# CPLD.net
KiCad netlist of a schematic drawn in Altium Designer
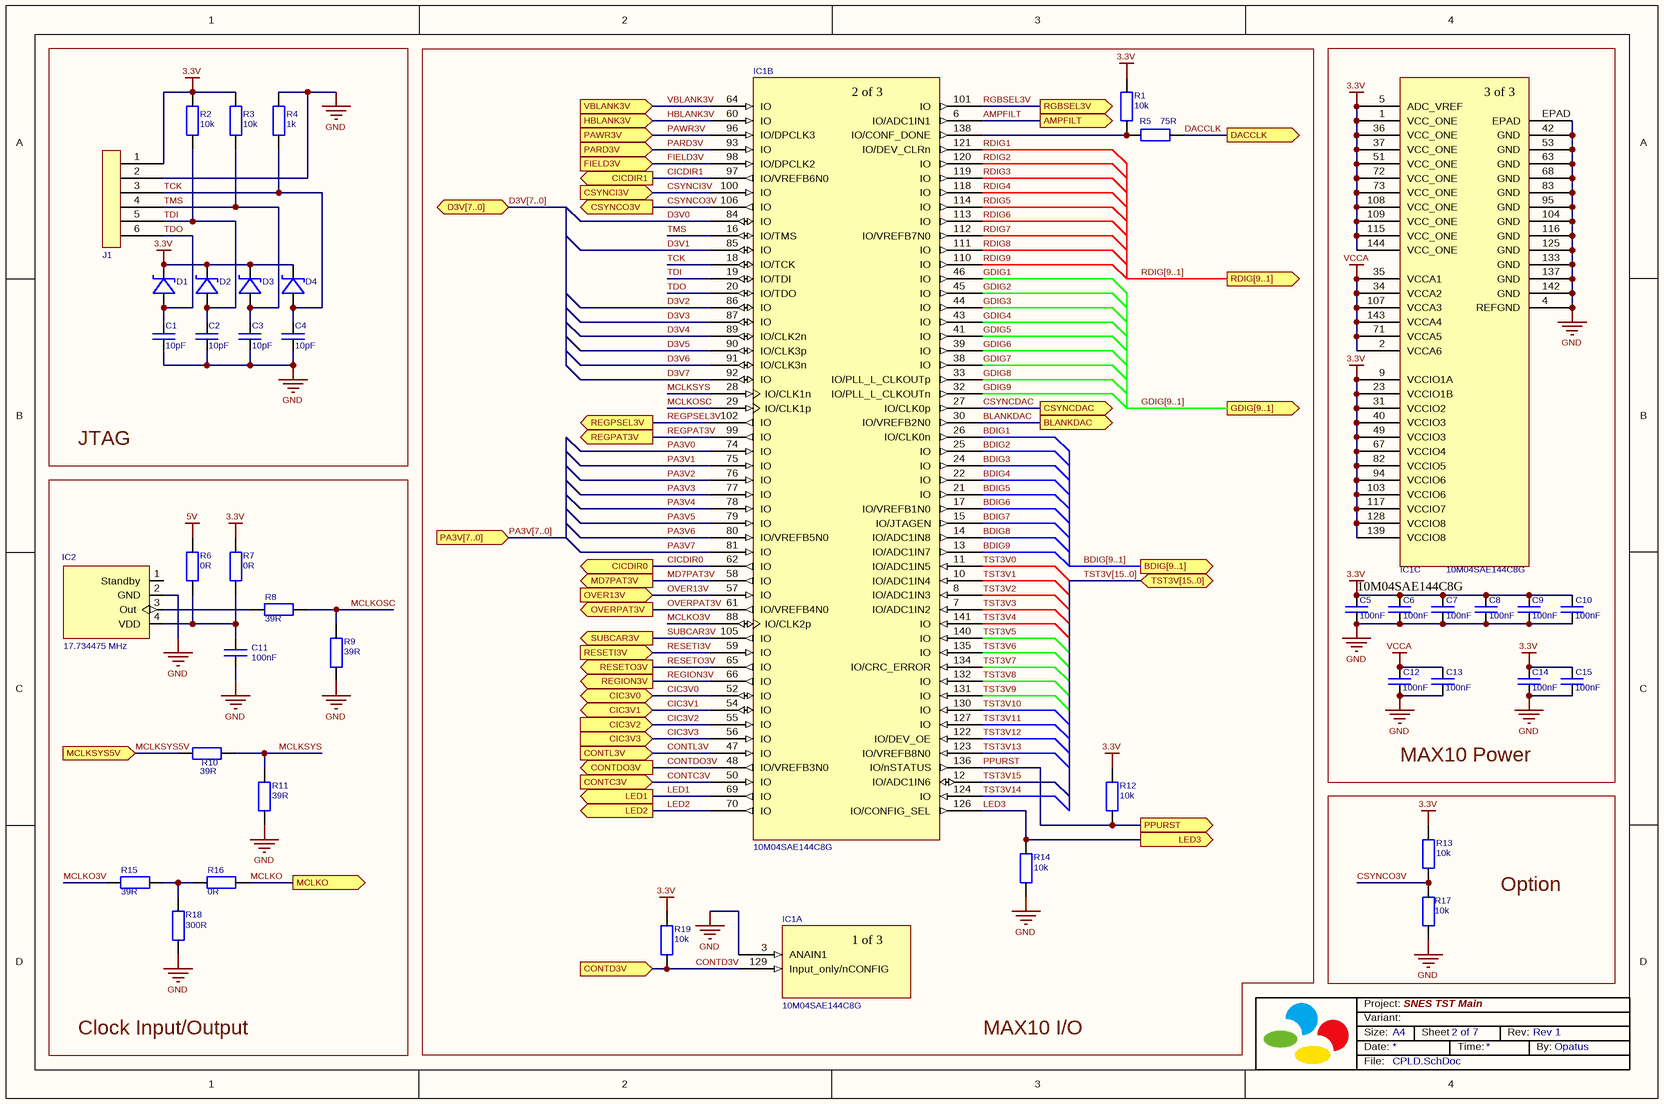
[diagram p0: CPLD.SchDoc]

(export (version "E")
  (design (tool "Eeschema 10.0.6"))
  (components
    (comp (ref "C1")
      (value "10pF")
      (footprint "Cap_0402_Chip")
      (fields
        (field (name "TOLERANCE") "±20%")
        (field (name "Comment") "Ceramic Capacitor 10pF 10V ±20% X7R 0402")
      )
      (libsource (lib "PCB") (part "Capacitor"))
    )
    (comp (ref "C2")
      (value "10pF")
      (footprint "Cap_0402_Chip")
      (fields
        (field (name "TOLERANCE") "±20%")
        (field (name "Comment") "Ceramic Capacitor 10pF 10V ±20% X7R 0402")
      )
      (libsource (lib "PCB") (part "Capacitor"))
    )
    (comp (ref "C3")
      (value "10pF")
      (footprint "Cap_0402_Chip")
      (fields
        (field (name "TOLERANCE") "±20%")
        (field (name "Comment") "Ceramic Capacitor 10pF 10V ±20% X7R 0402")
      )
      (libsource (lib "PCB") (part "Capacitor"))
    )
    (comp (ref "C4")
      (value "10pF")
      (footprint "Cap_0402_Chip")
      (fields
        (field (name "TOLERANCE") "±20%")
        (field (name "Comment") "Ceramic Capacitor 10pF 10V ±20% X7R 0402")
      )
      (libsource (lib "PCB") (part "Capacitor"))
    )
    (comp (ref "C5")
      (value "100nF")
      (footprint "Cap_0402_Chip")
      (fields
        (field (name "TOLERANCE") "±20%")
        (field (name "Comment") "Ceramic Capacitor 100nF 10V ±20% X7R 0402")
      )
      (libsource (lib "PCB") (part "Capacitor"))
    )
    (comp (ref "C6")
      (value "100nF")
      (footprint "Cap_0402_Chip")
      (fields
        (field (name "TOLERANCE") "±20%")
        (field (name "Comment") "Ceramic Capacitor 100nF 10V ±20% X7R 0402")
      )
      (libsource (lib "PCB") (part "Capacitor"))
    )
    (comp (ref "C7")
      (value "100nF")
      (footprint "Cap_0402_Chip")
      (fields
        (field (name "TOLERANCE") "±20%")
        (field (name "Comment") "Ceramic Capacitor 100nF 10V ±20% X7R 0402")
      )
      (libsource (lib "PCB") (part "Capacitor"))
    )
    (comp (ref "C8")
      (value "100nF")
      (footprint "Cap_0402_Chip")
      (fields
        (field (name "TOLERANCE") "±20%")
        (field (name "Comment") "Ceramic Capacitor 100nF 10V ±20% X7R 0402")
      )
      (libsource (lib "PCB") (part "Capacitor"))
    )
    (comp (ref "C9")
      (value "100nF")
      (footprint "Cap_0402_Chip")
      (fields
        (field (name "TOLERANCE") "±20%")
        (field (name "Comment") "Ceramic Capacitor 100nF 10V ±20% X7R 0402")
      )
      (libsource (lib "PCB") (part "Capacitor"))
    )
    (comp (ref "C10")
      (value "100nF")
      (footprint "Cap_0402_Chip")
      (fields
        (field (name "TOLERANCE") "±20%")
        (field (name "Comment") "Ceramic Capacitor 100nF 10V ±20% X7R 0402")
      )
      (libsource (lib "PCB") (part "Capacitor"))
    )
    (comp (ref "C11")
      (value "100nF")
      (footprint "Cap_0402_Chip")
      (fields
        (field (name "TOLERANCE") "±20%")
        (field (name "Comment") "Ceramic Capacitor 100nF 10V ±20% X7R 0402")
      )
      (libsource (lib "PCB") (part "Capacitor"))
    )
    (comp (ref "C12")
      (value "100nF")
      (footprint "Cap_0402_Chip")
      (fields
        (field (name "TOLERANCE") "±20%")
        (field (name "Comment") "Ceramic Capacitor 100nF 10V ±20% X7R 0402")
      )
      (libsource (lib "PCB") (part "Capacitor"))
    )
    (comp (ref "C13")
      (value "100nF")
      (footprint "Cap_0402_Chip")
      (fields
        (field (name "TOLERANCE") "±20%")
        (field (name "Comment") "Ceramic Capacitor 100nF 10V ±20% X7R 0402")
      )
      (libsource (lib "PCB") (part "Capacitor"))
    )
    (comp (ref "C14")
      (value "100nF")
      (footprint "Cap_0402_Chip")
      (fields
        (field (name "TOLERANCE") "±20%")
        (field (name "Comment") "Ceramic Capacitor 100nF 10V ±20% X7R 0402")
      )
      (libsource (lib "PCB") (part "Capacitor"))
    )
    (comp (ref "C15")
      (value "100nF")
      (footprint "Cap_0402_Chip")
      (fields
        (field (name "TOLERANCE") "±20%")
        (field (name "Comment") "Ceramic Capacitor 100nF 10V ±20% X7R 0402")
      )
      (libsource (lib "PCB") (part "Capacitor"))
    )
    (comp (ref "D1")
      (value "BAT54WS")
      (footprint "SOD323")
      (description "Schottky Diode")
      (fields (field (name "MANUFACTURER_PART_NUMBER") "BAT54WS-7-F") (field (name "MANUFACTURER") "Diodes"))
      (libsource (lib "PCB") (part "Schottky Diode"))
    )
    (comp (ref "D2")
      (value "BAT54WS")
      (footprint "SOD323")
      (description "Schottky Diode")
      (fields (field (name "MANUFACTURER_PART_NUMBER") "BAT54WS-7-F") (field (name "MANUFACTURER") "Diodes"))
      (libsource (lib "PCB") (part "Schottky Diode"))
    )
    (comp (ref "D3")
      (value "BAT54WS")
      (footprint "SOD323")
      (description "Schottky Diode")
      (fields (field (name "MANUFACTURER_PART_NUMBER") "BAT54WS-7-F") (field (name "MANUFACTURER") "Diodes"))
      (libsource (lib "PCB") (part "Schottky Diode"))
    )
    (comp (ref "D4")
      (value "BAT54WS")
      (footprint "SOD323")
      (description "Schottky Diode")
      (fields (field (name "MANUFACTURER_PART_NUMBER") "BAT54WS-7-F") (field (name "MANUFACTURER") "Diodes"))
      (libsource (lib "PCB") (part "Schottky Diode"))
    )
    (comp (ref "IC1")
      (value "10M04SAE144C8G")
      (footprint "EQFP-144_A:1P65_")
      (description "No Description Available")
      (fields
        (field (name "MANUFACTURER") "Intel")
        (field (name "MANUFACTURER_PART_NUMBER") "10M04SAE144C8G")
        (field (name "COPYRIGHT") "Copyright (C) 2018 Accelerated Designs. All rights reserved")
      )
      (libsource (lib "PCB") (part "10M08SAE144C8G"))
    )
    (comp (ref "IC2")
      (value "17.734475 MHz")
      (footprint "Quarz 7.5mm")
      (description "Oscillator")
      (fields
        (field (name "FREQUENCY") "17.734475 MHz")
        (field (name "MANUFACTURER") "IQD Frequency")
        (field (name "MANUFACTURER_PART_NUMBER") "LFSPXO020648Bulk")
      )
      (libsource (lib "PCB") (part "Oscillator"))
    )
    (comp (ref "J1")
      (value "Conn 6P")
      (footprint "Con6P")
      (description "6 Pole Connector")
      (libsource (lib "PCB") (part "Conn 6P"))
    )
    (comp (ref "R1")
      (value "10k")
      (footprint "Res_0402_Chip")
      (fields (field (name "TOLERANCE") "±1%") (field (name "Comment") "Resistor 10k 0402 ±1%"))
      (libsource (lib "PCB") (part "R"))
    )
    (comp (ref "R2")
      (value "10k")
      (footprint "Res_0402_Chip")
      (fields (field (name "TOLERANCE") "±1%") (field (name "Comment") "Resistor 10k 0402 ±1%"))
      (libsource (lib "PCB") (part "R"))
    )
    (comp (ref "R3")
      (value "10k")
      (footprint "Res_0402_Chip")
      (fields (field (name "TOLERANCE") "±1%") (field (name "Comment") "Resistor 10k 0402 ±1%"))
      (libsource (lib "PCB") (part "R"))
    )
    (comp (ref "R4")
      (value "1k")
      (footprint "Res_0402_Chip")
      (fields (field (name "TOLERANCE") "±1%") (field (name "Comment") "Resistor 1k 0402 ±1%"))
      (libsource (lib "") (part "R_3"))
    )
    (comp (ref "R5")
      (value "75R")
      (footprint "Res_0402_Chip")
      (fields (field (name "TOLERANCE") "±1%") (field (name "Comment") "Resistor 75R 0402 ±1%"))
      (libsource (lib "") (part "R_1"))
    )
    (comp (ref "R6")
      (value "0R")
      (footprint "Res_0402_Chip")
      (fields (field (name "Comment") "Resistor 0R 0402 "))
      (libsource (lib "PCB") (part "R"))
    )
    (comp (ref "R7")
      (value "0R")
      (footprint "Res_0402_Chip")
      (fields (field (name "Comment") "Resistor 0R 0402 "))
      (libsource (lib "PCB") (part "R"))
    )
    (comp (ref "R8")
      (value "39R")
      (footprint "Res_0603_Chip")
      (fields (field (name "TOLERANCE") "±1%") (field (name "Comment") "Resistor 39R 0603 ±1%"))
      (libsource (lib "") (part "R_2"))
    )
    (comp (ref "R9")
      (value "39R")
      (footprint "Res_0603_Chip")
      (fields (field (name "TOLERANCE") "±1%") (field (name "Comment") "Resistor 39R 0603 ±1%"))
      (libsource (lib "PCB") (part "R"))
    )
    (comp (ref "R10")
      (value "39R")
      (footprint "Res_0603_Chip")
      (fields (field (name "TOLERANCE") "±1%") (field (name "Comment") "Resistor 39R 0603 ±1%"))
      (libsource (lib "") (part "R_2"))
    )
    (comp (ref "R11")
      (value "39R")
      (footprint "Res_0603_Chip")
      (fields (field (name "TOLERANCE") "±1%") (field (name "Comment") "Resistor 39R 0603 ±1%"))
      (libsource (lib "PCB") (part "R"))
    )
    (comp (ref "R12")
      (value "10k")
      (footprint "Res_0402_Chip")
      (fields (field (name "TOLERANCE") "±1%") (field (name "Comment") "Resistor 10k 0402 ±1%"))
      (libsource (lib "PCB") (part "R"))
    )
    (comp (ref "R13")
      (value "10k")
      (footprint "Res_0402_Chip")
      (fields (field (name "TOLERANCE") "±1%") (field (name "Comment") "Resistor 10k 0402 ±1%"))
      (libsource (lib "PCB") (part "R"))
    )
    (comp (ref "R14")
      (value "10k")
      (footprint "Res_0402_Chip")
      (fields (field (name "TOLERANCE") "±1%") (field (name "Comment") "Resistor 10k 0402 ±1%"))
      (libsource (lib "") (part "R_3"))
    )
    (comp (ref "R15")
      (value "39R")
      (footprint "Res_0603_Chip")
      (fields (field (name "TOLERANCE") "±1%") (field (name "Comment") "Resistor 39R 0603 ±1%"))
      (libsource (lib "") (part "R_2"))
    )
    (comp (ref "R16")
      (value "0R")
      (footprint "Res_0603_Chip")
      (fields (field (name "Comment") "Resistor 0R 0603 "))
      (libsource (lib "") (part "R_2"))
    )
    (comp (ref "R17")
      (value "10k")
      (footprint "Res_0402_Chip")
      (fields (field (name "TOLERANCE") "±1%") (field (name "Comment") "Resistor 10k 0402 ±1%"))
      (libsource (lib "PCB") (part "R"))
    )
    (comp (ref "R18")
      (value "300R")
      (footprint "Res_0603_Chip")
      (fields (field (name "TOLERANCE") "±1%") (field (name "Comment") "Resistor 300R 0603 ±1%"))
      (libsource (lib "PCB") (part "R"))
    )
    (comp (ref "R19")
      (value "10k")
      (footprint "Res_0402_Chip")
      (fields (field (name "TOLERANCE") "±1%") (field (name "Comment") "Resistor 10k 0402 ±1%"))
      (libsource (lib "PCB") (part "R"))
    )
  )
  (nets
    (net (code "1") (name "/AMPFILT") (class "Default")
      (node (ref "IC1") (pin "6") (pinfunction "IO/ADC1IN1_6") (pintype "output"))
    )
    (net (code "2") (name "/BDIG1") (class "Default")
      (node (ref "IC1") (pin "26") (pinfunction "IO/CLK0n_26") (pintype "output"))
    )
    (net (code "3") (name "/BDIG2") (class "Default")
      (node (ref "IC1") (pin "25") (pinfunction "IO_25") (pintype "output"))
    )
    (net (code "4") (name "/BDIG3") (class "Default")
      (node (ref "IC1") (pin "24") (pinfunction "IO_24") (pintype "output"))
    )
    (net (code "5") (name "/BDIG4") (class "Default")
      (node (ref "IC1") (pin "22") (pinfunction "IO_22") (pintype "output"))
    )
    (net (code "6") (name "/BDIG5") (class "Default")
      (node (ref "IC1") (pin "21") (pinfunction "IO_21") (pintype "output"))
    )
    (net (code "7") (name "/BDIG6") (class "Default")
      (node (ref "IC1") (pin "17") (pinfunction "IO/VREFB1N0_17") (pintype "output"))
    )
    (net (code "8") (name "/BDIG7") (class "Default")
      (node (ref "IC1") (pin "15") (pinfunction "IO/JTAGEN_15") (pintype "output"))
    )
    (net (code "9") (name "/BDIG8") (class "Default")
      (node (ref "IC1") (pin "14") (pinfunction "IO/ADC1IN8_14") (pintype "output"))
    )
    (net (code "10") (name "/BDIG9") (class "Default")
      (node (ref "IC1") (pin "13") (pinfunction "IO/ADC1IN7_13") (pintype "output"))
    )
    (net (code "12") (name "/BLANKDAC") (class "Default")
      (node (ref "IC1") (pin "30") (pinfunction "IO/VREFB2N0_30") (pintype "output"))
    )
    (net (code "13") (name "/CIC3V0") (class "Default")
      (node (ref "IC1") (pin "52") (pinfunction "IO_52") (pintype "bidirectional"))
    )
    (net (code "14") (name "/CIC3V1") (class "Default")
      (node (ref "IC1") (pin "54") (pinfunction "IO_54") (pintype "bidirectional"))
    )
    (net (code "15") (name "/CIC3V2") (class "Default")
      (node (ref "IC1") (pin "55") (pinfunction "IO_55") (pintype "input"))
    )
    (net (code "16") (name "/CIC3V3") (class "Default")
      (node (ref "IC1") (pin "56") (pinfunction "IO_56") (pintype "input"))
    )
    (net (code "17") (name "/CICDIR0") (class "Default")
      (node (ref "IC1") (pin "62") (pinfunction "IO_62") (pintype "output"))
    )
    (net (code "18") (name "/CICDIR1") (class "Default")
      (node (ref "IC1") (pin "97") (pinfunction "IO/VREFB6N0_97") (pintype "output"))
    )
    (net (code "19") (name "/CONTC3V") (class "Default")
      (node (ref "IC1") (pin "50") (pinfunction "IO_50") (pintype "input"))
    )
    (net (code "20") (name "/CONTD3V") (class "Default")
      (node (ref "IC1") (pin "129") (pinfunction "Input_only/nCONFIG_129") (pintype "input"))
      (node (ref "R19") (pin "2") (pintype "passive"))
    )
    (net (code "21") (name "/CONTDO3V") (class "Default")
      (node (ref "IC1") (pin "48") (pinfunction "IO/VREFB3N0_48") (pintype "output"))
    )
    (net (code "22") (name "/CONTL3V") (class "Default")
      (node (ref "IC1") (pin "47") (pinfunction "IO_47") (pintype "input"))
    )
    (net (code "23") (name "/CSYNCDAC") (class "Default")
      (node (ref "IC1") (pin "27") (pinfunction "IO/CLK0p_27") (pintype "output"))
    )
    (net (code "24") (name "/CSYNCI3V") (class "Default")
      (node (ref "IC1") (pin "100") (pinfunction "IO_100") (pintype "input"))
    )
    (net (code "25") (name "/CSYNCO3V") (class "Default")
      (node (ref "IC1") (pin "106") (pinfunction "IO_106") (pintype "output"))
      (node (ref "R13") (pin "2") (pintype "passive"))
      (node (ref "R17") (pin "1") (pintype "passive"))
    )
    (net (code "26") (name "/D3V0") (class "Default")
      (node (ref "IC1") (pin "84") (pinfunction "IO_84") (pintype "bidirectional"))
    )
    (net (code "27") (name "/D3V1") (class "Default")
      (node (ref "IC1") (pin "85") (pinfunction "IO_85") (pintype "bidirectional"))
    )
    (net (code "28") (name "/D3V2") (class "Default")
      (node (ref "IC1") (pin "86") (pinfunction "IO_86") (pintype "bidirectional"))
    )
    (net (code "29") (name "/D3V3") (class "Default")
      (node (ref "IC1") (pin "87") (pinfunction "IO_87") (pintype "bidirectional"))
    )
    (net (code "30") (name "/D3V4") (class "Default")
      (node (ref "IC1") (pin "89") (pinfunction "IO/CLK2n_89") (pintype "bidirectional"))
    )
    (net (code "31") (name "/D3V5") (class "Default")
      (node (ref "IC1") (pin "90") (pinfunction "IO/CLK3p_90") (pintype "bidirectional"))
    )
    (net (code "32") (name "/D3V6") (class "Default")
      (node (ref "IC1") (pin "91") (pinfunction "IO/CLK3n_91") (pintype "bidirectional"))
    )
    (net (code "33") (name "/D3V7") (class "Default")
      (node (ref "IC1") (pin "92") (pinfunction "IO_92") (pintype "bidirectional"))
    )
    (net (code "35") (name "/DACCLK") (class "Default") (node (ref "R5") (pin "2") (pintype "passive")))
    (net (code "36") (name "/FIELD3V") (class "Default")
      (node (ref "IC1") (pin "98") (pinfunction "IO/DPCLK2_98") (pintype "input"))
    )
    (net (code "37") (name "/GDIG1") (class "Default")
      (node (ref "IC1") (pin "46") (pinfunction "IO_46") (pintype "output"))
    )
    (net (code "38") (name "/GDIG2") (class "Default")
      (node (ref "IC1") (pin "45") (pinfunction "IO_45") (pintype "output"))
    )
    (net (code "39") (name "/GDIG3") (class "Default")
      (node (ref "IC1") (pin "44") (pinfunction "IO_44") (pintype "output"))
    )
    (net (code "40") (name "/GDIG4") (class "Default")
      (node (ref "IC1") (pin "43") (pinfunction "IO_43") (pintype "output"))
    )
    (net (code "41") (name "/GDIG5") (class "Default")
      (node (ref "IC1") (pin "41") (pinfunction "IO_41") (pintype "output"))
    )
    (net (code "42") (name "/GDIG6") (class "Default")
      (node (ref "IC1") (pin "39") (pinfunction "IO_39") (pintype "output"))
    )
    (net (code "43") (name "/GDIG7") (class "Default")
      (node (ref "IC1") (pin "38") (pinfunction "IO_38") (pintype "output"))
    )
    (net (code "44") (name "/GDIG8") (class "Default")
      (node (ref "IC1") (pin "33") (pinfunction "IO/PLL_L_CLKOUTp_33") (pintype "output"))
    )
    (net (code "45") (name "/GDIG9") (class "Default")
      (node (ref "IC1") (pin "32") (pinfunction "IO/PLL_L_CLKOUTn_32") (pintype "output"))
    )
    (net (code "47") (name "/HBLANK3V") (class "Default")
      (node (ref "IC1") (pin "60") (pinfunction "IO_60") (pintype "input"))
    )
    (net (code "48") (name "/LED1") (class "Default")
      (node (ref "IC1") (pin "69") (pinfunction "IO_69") (pintype "output"))
    )
    (net (code "49") (name "/LED2") (class "Default")
      (node (ref "IC1") (pin "70") (pinfunction "IO_70") (pintype "output"))
    )
    (net (code "50") (name "/LED3") (class "Default")
      (node (ref "IC1") (pin "126") (pinfunction "IO/CONFIG_SEL_126") (pintype "output"))
      (node (ref "R14") (pin "2") (pintype "passive"))
    )
    (net (code "51") (name "/MCLKO") (class "Default") (node (ref "R16") (pin "1") (pintype "passive")))
    (net (code "52") (name "/MCLKO3V") (class "Default")
      (node (ref "IC1") (pin "88") (pinfunction "IO/CLK2p_88") (pintype "bidirectional"))
      (node (ref "R15") (pin "2") (pintype "passive"))
    )
    (net (code "53") (name "/MCLKOSC") (class "Default")
      (node (ref "IC1") (pin "29") (pinfunction "IO/CLK1p_29") (pintype "input"))
      (node (ref "R8") (pin "1") (pintype "passive"))
      (node (ref "R9") (pin "1") (pintype "passive"))
    )
    (net (code "54") (name "/MCLKSYS") (class "Default")
      (node (ref "IC1") (pin "28") (pinfunction "IO/CLK1n_28") (pintype "input"))
      (node (ref "R10") (pin "1") (pintype "passive"))
      (node (ref "R11") (pin "1") (pintype "passive"))
    )
    (net (code "55") (name "/MCLKSYS5V") (class "Default") (node (ref "R10") (pin "2") (pintype "passive")))
    (net (code "56") (name "/MD7PAT3V") (class "Default")
      (node (ref "IC1") (pin "58") (pinfunction "IO_58") (pintype "output"))
    )
    (net (code "57") (name "/OVER13V") (class "Default")
      (node (ref "IC1") (pin "57") (pinfunction "IO_57") (pintype "input"))
    )
    (net (code "58") (name "/OVERPAT3V") (class "Default")
      (node (ref "IC1") (pin "61") (pinfunction "IO/VREFB4N0_61") (pintype "output"))
    )
    (net (code "59") (name "/PA3V0") (class "Default")
      (node (ref "IC1") (pin "74") (pinfunction "IO_74") (pintype "input"))
    )
    (net (code "60") (name "/PA3V1") (class "Default")
      (node (ref "IC1") (pin "75") (pinfunction "IO_75") (pintype "input"))
    )
    (net (code "61") (name "/PA3V2") (class "Default")
      (node (ref "IC1") (pin "76") (pinfunction "IO_76") (pintype "input"))
    )
    (net (code "62") (name "/PA3V3") (class "Default")
      (node (ref "IC1") (pin "77") (pinfunction "IO_77") (pintype "input"))
    )
    (net (code "63") (name "/PA3V4") (class "Default")
      (node (ref "IC1") (pin "78") (pinfunction "IO_78") (pintype "input"))
    )
    (net (code "64") (name "/PA3V5") (class "Default")
      (node (ref "IC1") (pin "79") (pinfunction "IO_79") (pintype "input"))
    )
    (net (code "65") (name "/PA3V6") (class "Default")
      (node (ref "IC1") (pin "80") (pinfunction "IO/VREFB5N0_80") (pintype "input"))
    )
    (net (code "66") (name "/PA3V7") (class "Default")
      (node (ref "IC1") (pin "81") (pinfunction "IO_81") (pintype "input"))
    )
    (net (code "68") (name "/PARD3V") (class "Default")
      (node (ref "IC1") (pin "93") (pinfunction "IO_93") (pintype "input"))
    )
    (net (code "69") (name "/PAWR3V") (class "Default")
      (node (ref "IC1") (pin "96") (pinfunction "IO/DPCLK3_96") (pintype "input"))
    )
    (net (code "70") (name "/PPURST") (class "Default")
      (node (ref "IC1") (pin "136") (pinfunction "IO/nSTATUS_136") (pintype "output"))
      (node (ref "R12") (pin "2") (pintype "passive"))
    )
    (net (code "71") (name "/RDIG1") (class "Default")
      (node (ref "IC1") (pin "121") (pinfunction "IO/DEV_CLRn_121") (pintype "output"))
    )
    (net (code "72") (name "/RDIG2") (class "Default")
      (node (ref "IC1") (pin "120") (pinfunction "IO_120") (pintype "output"))
    )
    (net (code "73") (name "/RDIG3") (class "Default")
      (node (ref "IC1") (pin "119") (pinfunction "IO_119") (pintype "output"))
    )
    (net (code "74") (name "/RDIG4") (class "Default")
      (node (ref "IC1") (pin "118") (pinfunction "IO_118") (pintype "output"))
    )
    (net (code "75") (name "/RDIG5") (class "Default")
      (node (ref "IC1") (pin "114") (pinfunction "IO_114") (pintype "output"))
    )
    (net (code "76") (name "/RDIG6") (class "Default")
      (node (ref "IC1") (pin "113") (pinfunction "IO_113") (pintype "output"))
    )
    (net (code "77") (name "/RDIG7") (class "Default")
      (node (ref "IC1") (pin "112") (pinfunction "IO/VREFB7N0_112") (pintype "output"))
    )
    (net (code "78") (name "/RDIG8") (class "Default")
      (node (ref "IC1") (pin "111") (pinfunction "IO_111") (pintype "output"))
    )
    (net (code "79") (name "/RDIG9") (class "Default")
      (node (ref "IC1") (pin "110") (pinfunction "IO_110") (pintype "output"))
    )
    (net (code "81") (name "/REGION3V") (class "Default")
      (node (ref "IC1") (pin "66") (pinfunction "IO_66") (pintype "output"))
    )
    (net (code "82") (name "/REGPAT3V") (class "Default")
      (node (ref "IC1") (pin "99") (pinfunction "IO_99") (pintype "output"))
    )
    (net (code "83") (name "/REGPSEL3V") (class "Default")
      (node (ref "IC1") (pin "102") (pinfunction "IO_102") (pintype "output"))
    )
    (net (code "84") (name "/RESETI3V") (class "Default")
      (node (ref "IC1") (pin "59") (pinfunction "IO_59") (pintype "input"))
    )
    (net (code "85") (name "/RESETO3V") (class "Default")
      (node (ref "IC1") (pin "65") (pinfunction "IO_65") (pintype "output"))
    )
    (net (code "86") (name "/RGBSEL3V") (class "Default")
      (node (ref "IC1") (pin "101") (pinfunction "IO_101") (pintype "output"))
    )
    (net (code "87") (name "/SUBCAR3V") (class "Default")
      (node (ref "IC1") (pin "105") (pinfunction "IO_105") (pintype "output"))
    )
    (net (code "88") (name "/TCK") (class "Default")
      (node (ref "C4") (pin "1") (pintype "passive"))
      (node (ref "D4") (pin "2") (pinfunction "A_2") (pintype "passive"))
      (node (ref "IC1") (pin "18") (pinfunction "IO/TCK_18") (pintype "bidirectional"))
      (node (ref "J1") (pin "3") (pintype "passive"))
      (node (ref "R4") (pin "1") (pintype "passive"))
    )
    (net (code "89") (name "/TDI") (class "Default")
      (node (ref "C2") (pin "1") (pintype "passive"))
      (node (ref "D2") (pin "2") (pinfunction "A_2") (pintype "passive"))
      (node (ref "IC1") (pin "19") (pinfunction "IO/TDI_19") (pintype "bidirectional"))
      (node (ref "J1") (pin "5") (pintype "passive"))
      (node (ref "R2") (pin "2") (pintype "passive"))
    )
    (net (code "90") (name "/TDO") (class "Default")
      (node (ref "C1") (pin "1") (pintype "passive"))
      (node (ref "D1") (pin "2") (pinfunction "A_2") (pintype "passive"))
      (node (ref "IC1") (pin "20") (pinfunction "IO/TDO_20") (pintype "bidirectional"))
      (node (ref "J1") (pin "6") (pintype "passive"))
    )
    (net (code "91") (name "/TMS") (class "Default")
      (node (ref "C3") (pin "1") (pintype "passive"))
      (node (ref "D3") (pin "2") (pinfunction "A_2") (pintype "passive"))
      (node (ref "IC1") (pin "16") (pinfunction "IO/TMS_16") (pintype "bidirectional"))
      (node (ref "J1") (pin "4") (pintype "passive"))
      (node (ref "R3") (pin "2") (pintype "passive"))
    )
    (net (code "92") (name "/TST3V0") (class "Default")
      (node (ref "IC1") (pin "11") (pinfunction "IO/ADC1IN5_11") (pintype "input"))
    )
    (net (code "93") (name "/TST3V1") (class "Default")
      (node (ref "IC1") (pin "10") (pinfunction "IO/ADC1IN4_10") (pintype "input"))
    )
    (net (code "94") (name "/TST3V2") (class "Default")
      (node (ref "IC1") (pin "8") (pinfunction "IO/ADC1IN3_8") (pintype "input"))
    )
    (net (code "95") (name "/TST3V3") (class "Default")
      (node (ref "IC1") (pin "7") (pinfunction "IO/ADC1IN2_7") (pintype "input"))
    )
    (net (code "96") (name "/TST3V4") (class "Default")
      (node (ref "IC1") (pin "141") (pinfunction "IO_141") (pintype "input"))
    )
    (net (code "97") (name "/TST3V5") (class "Default")
      (node (ref "IC1") (pin "140") (pinfunction "IO_140") (pintype "input"))
    )
    (net (code "98") (name "/TST3V6") (class "Default")
      (node (ref "IC1") (pin "135") (pinfunction "IO_135") (pintype "input"))
    )
    (net (code "99") (name "/TST3V7") (class "Default")
      (node (ref "IC1") (pin "134") (pinfunction "IO/CRC_ERROR_134") (pintype "input"))
    )
    (net (code "100") (name "/TST3V8") (class "Default")
      (node (ref "IC1") (pin "132") (pinfunction "IO_132") (pintype "input"))
    )
    (net (code "101") (name "/TST3V9") (class "Default")
      (node (ref "IC1") (pin "131") (pinfunction "IO_131") (pintype "input"))
    )
    (net (code "102") (name "/TST3V10") (class "Default")
      (node (ref "IC1") (pin "130") (pinfunction "IO_130") (pintype "input"))
    )
    (net (code "103") (name "/TST3V11") (class "Default")
      (node (ref "IC1") (pin "127") (pinfunction "IO_127") (pintype "input"))
    )
    (net (code "104") (name "/TST3V12") (class "Default")
      (node (ref "IC1") (pin "122") (pinfunction "IO/DEV_OE_122") (pintype "input"))
    )
    (net (code "105") (name "/TST3V13") (class "Default")
      (node (ref "IC1") (pin "123") (pinfunction "IO/VREFB8N0_123") (pintype "input"))
    )
    (net (code "106") (name "/TST3V14") (class "Default")
      (node (ref "IC1") (pin "124") (pinfunction "IO_124") (pintype "input"))
    )
    (net (code "107") (name "/TST3V15") (class "Default")
      (node (ref "IC1") (pin "12") (pinfunction "IO/ADC1IN6_12") (pintype "bidirectional"))
    )
    (net (code "109") (name "/VBLANK3V") (class "Default")
      (node (ref "IC1") (pin "64") (pinfunction "IO_64") (pintype "input"))
    )
    (net (code "110") (name "3.3V") (class "Default")
      (node (ref "C10") (pin "1") (pintype "passive"))
      (node (ref "C14") (pin "1") (pintype "passive"))
      (node (ref "C15") (pin "1") (pintype "passive"))
      (node (ref "C5") (pin "1") (pintype "passive"))
      (node (ref "C6") (pin "1") (pintype "passive"))
      (node (ref "C7") (pin "1") (pintype "passive"))
      (node (ref "C8") (pin "1") (pintype "passive"))
      (node (ref "C9") (pin "1") (pintype "passive"))
      (node (ref "D1") (pin "1") (pinfunction "K_1") (pintype "passive"))
      (node (ref "D2") (pin "1") (pinfunction "K_1") (pintype "passive"))
      (node (ref "D3") (pin "1") (pinfunction "K_1") (pintype "passive"))
      (node (ref "D4") (pin "1") (pinfunction "K_1") (pintype "passive"))
      (node (ref "IC1") (pin "1") (pinfunction "VCC_ONE_1") (pintype "power_in"))
      (node (ref "IC1") (pin "103") (pinfunction "VCCIO6_103") (pintype "power_in"))
      (node (ref "IC1") (pin "108") (pinfunction "VCC_ONE_108") (pintype "power_in"))
      (node (ref "IC1") (pin "109") (pinfunction "VCC_ONE_109") (pintype "power_in"))
      (node (ref "IC1") (pin "115") (pinfunction "VCC_ONE_115") (pintype "power_in"))
      (node (ref "IC1") (pin "117") (pinfunction "VCCIO7_117") (pintype "power_in"))
      (node (ref "IC1") (pin "128") (pinfunction "VCCIO8_128") (pintype "power_in"))
      (node (ref "IC1") (pin "139") (pinfunction "VCCIO8_139") (pintype "power_in"))
      (node (ref "IC1") (pin "144") (pinfunction "VCC_ONE_144") (pintype "power_in"))
      (node (ref "IC1") (pin "23") (pinfunction "VCCIO1B_23") (pintype "power_in"))
      (node (ref "IC1") (pin "31") (pinfunction "VCCIO2_31") (pintype "power_in"))
      (node (ref "IC1") (pin "36") (pinfunction "VCC_ONE_36") (pintype "power_in"))
      (node (ref "IC1") (pin "37") (pinfunction "VCC_ONE_37") (pintype "power_in"))
      (node (ref "IC1") (pin "40") (pinfunction "VCCIO3_40") (pintype "power_in"))
      (node (ref "IC1") (pin "49") (pinfunction "VCCIO3_49") (pintype "power_in"))
      (node (ref "IC1") (pin "5") (pinfunction "ADC_VREF_5") (pintype "power_in"))
      (node (ref "IC1") (pin "51") (pinfunction "VCC_ONE_51") (pintype "power_in"))
      (node (ref "IC1") (pin "67") (pinfunction "VCCIO4_67") (pintype "power_in"))
      (node (ref "IC1") (pin "72") (pinfunction "VCC_ONE_72") (pintype "power_in"))
      (node (ref "IC1") (pin "73") (pinfunction "VCC_ONE_73") (pintype "power_in"))
      (node (ref "IC1") (pin "82") (pinfunction "VCCIO5_82") (pintype "power_in"))
      (node (ref "IC1") (pin "9") (pinfunction "VCCIO1A_9") (pintype "power_in"))
      (node (ref "IC1") (pin "94") (pinfunction "VCCIO6_94") (pintype "power_in"))
      (node (ref "J1") (pin "1") (pintype "passive"))
      (node (ref "R1") (pin "1") (pintype "passive"))
      (node (ref "R12") (pin "1") (pintype "passive"))
      (node (ref "R13") (pin "1") (pintype "passive"))
      (node (ref "R19") (pin "1") (pintype "passive"))
      (node (ref "R2") (pin "1") (pintype "passive"))
      (node (ref "R3") (pin "1") (pintype "passive"))
      (node (ref "R7") (pin "1") (pintype "passive"))
    )
    (net (code "111") (name "5V") (class "Default") (node (ref "R6") (pin "1") (pintype "passive")))
    (net (code "112") (name "GND") (class "Default")
      (node (ref "C1") (pin "2") (pintype "passive"))
      (node (ref "C10") (pin "2") (pintype "passive"))
      (node (ref "C11") (pin "2") (pintype "passive"))
      (node (ref "C12") (pin "2") (pintype "passive"))
      (node (ref "C13") (pin "2") (pintype "passive"))
      (node (ref "C14") (pin "2") (pintype "passive"))
      (node (ref "C15") (pin "2") (pintype "passive"))
      (node (ref "C2") (pin "2") (pintype "passive"))
      (node (ref "C3") (pin "2") (pintype "passive"))
      (node (ref "C4") (pin "2") (pintype "passive"))
      (node (ref "C5") (pin "2") (pintype "passive"))
      (node (ref "C6") (pin "2") (pintype "passive"))
      (node (ref "C7") (pin "2") (pintype "passive"))
      (node (ref "C8") (pin "2") (pintype "passive"))
      (node (ref "C9") (pin "2") (pintype "passive"))
      (node (ref "IC1") (pin "104") (pinfunction "GND_104") (pintype "power_in"))
      (node (ref "IC1") (pin "116") (pinfunction "GND_116") (pintype "power_in"))
      (node (ref "IC1") (pin "125") (pinfunction "GND_125") (pintype "power_in"))
      (node (ref "IC1") (pin "133") (pinfunction "GND_133") (pintype "power_in"))
      (node (ref "IC1") (pin "137") (pinfunction "GND_137") (pintype "power_in"))
      (node (ref "IC1") (pin "142") (pinfunction "GND_142") (pintype "power_in"))
      (node (ref "IC1") (pin "3") (pinfunction "ANAIN1_3") (pintype "input"))
      (node (ref "IC1") (pin "4") (pinfunction "REFGND_4") (pintype "power_in"))
      (node (ref "IC1") (pin "42") (pinfunction "GND_42") (pintype "power_in"))
      (node (ref "IC1") (pin "53") (pinfunction "GND_53") (pintype "power_in"))
      (node (ref "IC1") (pin "63") (pinfunction "GND_63") (pintype "power_in"))
      (node (ref "IC1") (pin "68") (pinfunction "GND_68") (pintype "power_in"))
      (node (ref "IC1") (pin "83") (pinfunction "GND_83") (pintype "power_in"))
      (node (ref "IC1") (pin "95") (pinfunction "GND_95") (pintype "power_in"))
      (node (ref "IC1") (pin "EPAD") (pinfunction "EPAD_EPAD") (pintype "power_in"))
      (node (ref "IC2") (pin "2") (pinfunction "GND_2") (pintype "passive"))
      (node (ref "J1") (pin "2") (pintype "passive"))
      (node (ref "R11") (pin "2") (pintype "passive"))
      (node (ref "R14") (pin "1") (pintype "passive"))
      (node (ref "R17") (pin "2") (pintype "passive"))
      (node (ref "R18") (pin "2") (pintype "passive"))
      (node (ref "R4") (pin "2") (pintype "passive"))
      (node (ref "R9") (pin "2") (pintype "passive"))
    )
    (net (code "113") (name "Net-(IC1B-IO{slash}CONF_DONE)") (class "Default")
      (node (ref "IC1") (pin "138") (pinfunction "IO/CONF_DONE_138") (pintype "output"))
      (node (ref "R1") (pin "2") (pintype "passive"))
      (node (ref "R5") (pin "1") (pintype "passive"))
    )
    (net (code "114") (name "Net-(IC2-Out)") (class "Default")
      (node (ref "IC2") (pin "3") (pinfunction "Out_3") (pintype "output"))
      (node (ref "R8") (pin "2") (pintype "passive"))
    )
    (net (code "115") (name "Net-(IC2-VDD)") (class "Default")
      (node (ref "C11") (pin "1") (pintype "passive"))
      (node (ref "IC2") (pin "4") (pinfunction "VDD_4") (pintype "passive"))
      (node (ref "R6") (pin "2") (pintype "passive"))
      (node (ref "R7") (pin "2") (pintype "passive"))
    )
    (net (code "116") (name "Net-(R15-Pad1)") (class "Default")
      (node (ref "R15") (pin "1") (pintype "passive"))
      (node (ref "R16") (pin "2") (pintype "passive"))
      (node (ref "R18") (pin "1") (pintype "passive"))
    )
    (net (code "117") (name "VCCA") (class "Default")
      (node (ref "C12") (pin "1") (pintype "passive"))
      (node (ref "C13") (pin "1") (pintype "passive"))
      (node (ref "IC1") (pin "107") (pinfunction "VCCA3_107") (pintype "power_in"))
      (node (ref "IC1") (pin "143") (pinfunction "VCCA4_143") (pintype "power_in"))
      (node (ref "IC1") (pin "2") (pinfunction "VCCA6_2") (pintype "power_in"))
      (node (ref "IC1") (pin "34") (pinfunction "VCCA2_34") (pintype "power_in"))
      (node (ref "IC1") (pin "35") (pinfunction "VCCA1_35") (pintype "power_in"))
      (node (ref "IC1") (pin "71") (pinfunction "VCCA5_71") (pintype "power_in"))
    )
    (net (code "118") (name "unconnected-(IC2-Standby-Pad1)") (class "Default")
      (node (ref "IC2") (pin "1") (pinfunction "Standby_1") (pintype "passive"))
    )
  )
)
